# MCU.net
KiCad netlist of a schematic drawn in Altium Designer
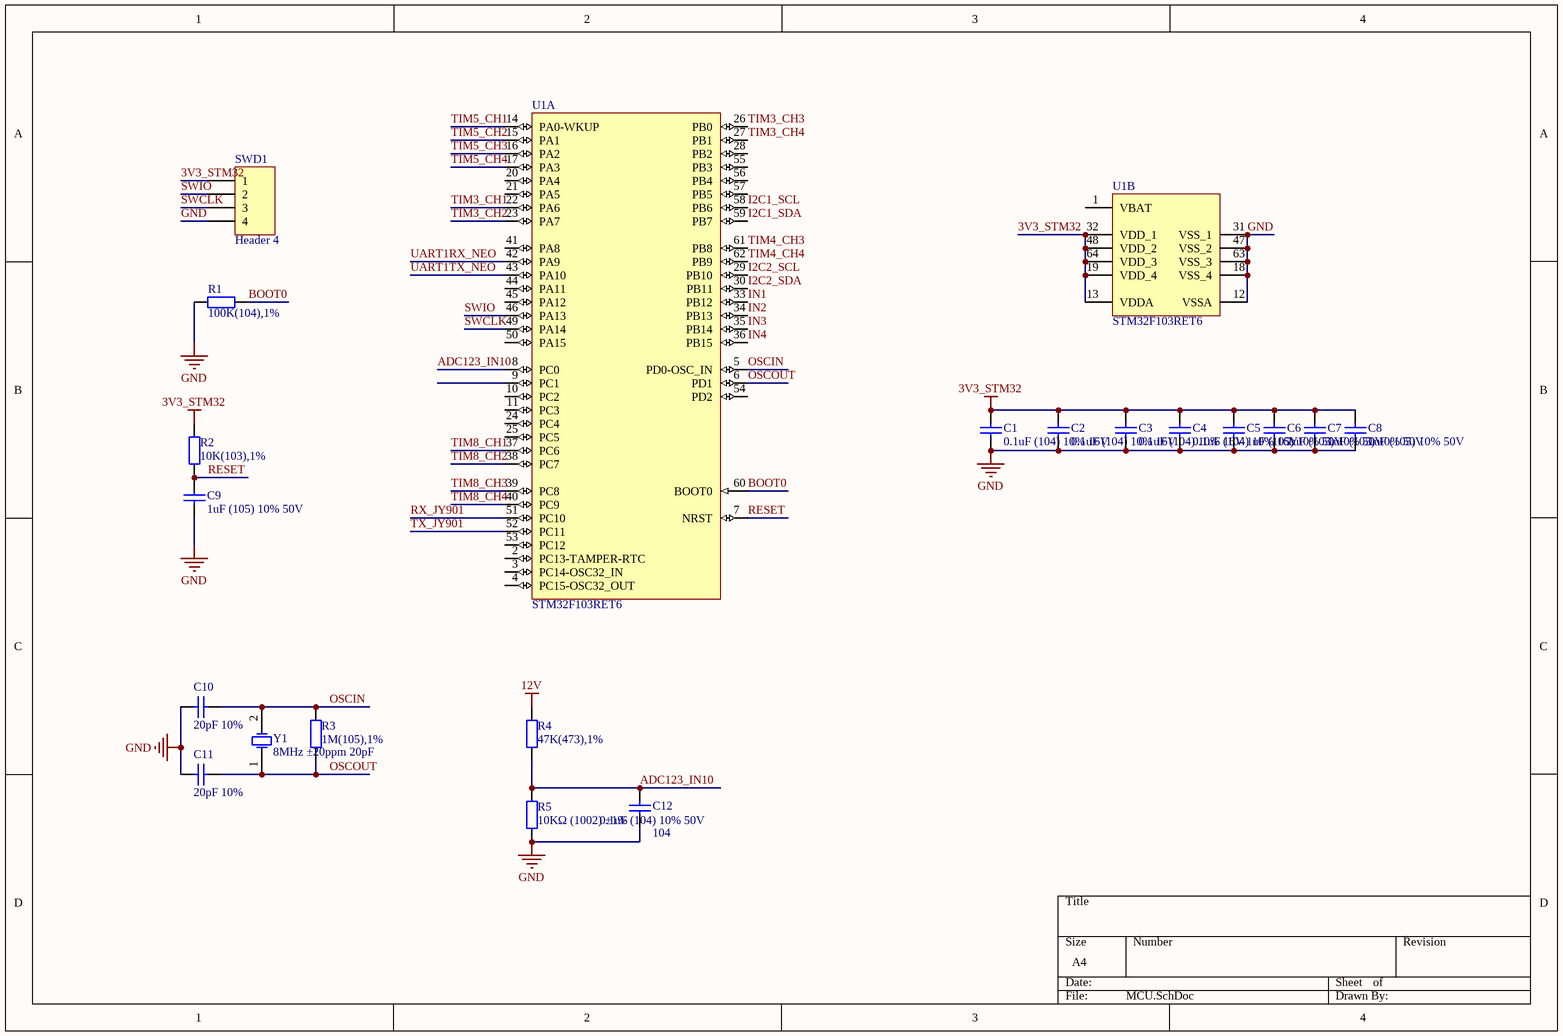
[diagram p0: MCU.SchDoc]

(export (version "E")
  (design (tool "Eeschema 10.0.6"))
  (components
    (comp (ref "C1")
      (value "0.1uF (104) 10% 16V")
      (footprint "0603_C")
      (description "Capacitor")
      (fields (field (name "PUBLISHER") "Altium Limited"))
      (libsource (lib "STM32F103C8T6(原理图库)") (part "Cap"))
    )
    (comp (ref "C2")
      (value "0.1uF (104) 10% 16V")
      (footprint "0603_C")
      (description "Capacitor")
      (fields (field (name "PUBLISHER") "Altium Limited"))
      (libsource (lib "STM32F103C8T6(原理图库)") (part "Cap"))
    )
    (comp (ref "C3")
      (value "0.1uF (104) 10% 16V")
      (footprint "0603_C")
      (description "Capacitor")
      (fields (field (name "PUBLISHER") "Altium Limited"))
      (libsource (lib "STM32F103C8T6(原理图库)") (part "Cap"))
    )
    (comp (ref "C4")
      (value "0.1uF (104) 10% 16V")
      (footprint "0603_C")
      (description "Capacitor")
      (fields (field (name "PUBLISHER") "Altium Limited"))
      (libsource (lib "STM32F103C8T6(原理图库)") (part "Cap"))
    )
    (comp (ref "C5")
      (value "1uF (105) 10% 50V")
      (footprint "0603_C")
      (description "贴片电容")
      (libsource (lib "Miscellaneous Devices LC") (part "0603 1uF (105) 10% 50V"))
    )
    (comp (ref "C6")
      (value "1uF (105) 10% 50V")
      (footprint "0603_C")
      (description "贴片电容")
      (libsource (lib "Miscellaneous Devices LC") (part "0603 1uF (105) 10% 50V"))
    )
    (comp (ref "C7")
      (value "1uF (105) 10% 50V")
      (footprint "0603_C")
      (description "贴片电容")
      (libsource (lib "Miscellaneous Devices LC") (part "0603 1uF (105) 10% 50V"))
    )
    (comp (ref "C8")
      (value "1uF (105) 10% 50V")
      (footprint "0603_C")
      (description "贴片电容")
      (libsource (lib "Miscellaneous Devices LC") (part "0603 1uF (105) 10% 50V"))
    )
    (comp (ref "C9")
      (value "1uF (105) 10% 50V")
      (footprint "0603_C")
      (description "Capacitor")
      (fields (field (name "PUBLISHER") "Altium Limited"))
      (libsource (lib "STM32F103C8T6(原理图库)") (part "Cap"))
    )
    (comp (ref "C10")
      (value "20pF 10%")
      (footprint "0603_C")
      (description "Capacitor")
      (fields (field (name "PUBLISHER") "Altium Limited"))
      (libsource (lib "STM32F103C8T6(原理图库)") (part "Cap"))
    )
    (comp (ref "C11")
      (value "20pF 10%")
      (footprint "0603_C")
      (description "Capacitor")
      (fields (field (name "PUBLISHER") "Altium Limited"))
      (libsource (lib "STM32F103C8T6(原理图库)") (part "Cap"))
    )
    (comp (ref "C12")
      (value "0.1uF (104) 10% 50V")
      (footprint "0603_C")
      (description "Capacitor")
      (fields (field (name "ALTIUM_VALUE") "104") (field (name "PUBLISHER") "Altium Limited"))
      (libsource (lib "Miscellaneous Devices") (part "Cap"))
    )
    (comp (ref "R1")
      (value "100K(104),1%")
      (footprint "0603_R")
      (description "Resistor")
      (fields (field (name "PUBLISHER") "Altium Limited"))
      (libsource (lib "") (part "Res2_1"))
    )
    (comp (ref "R2")
      (value "10K(103),1%")
      (footprint "0603_R")
      (description "Resistor")
      (fields (field (name "PUBLISHER") "Altium Limited"))
      (libsource (lib "STM32F103C8T6(原理图库)") (part "Res2"))
    )
    (comp (ref "R3")
      (value "1M(105),1%")
      (footprint "0603_R")
      (description "Resistor")
      (fields (field (name "PUBLISHER") "Altium Limited"))
      (libsource (lib "STM32F103C8T6(原理图库)") (part "Res2"))
    )
    (comp (ref "R4")
      (value "47K(473),1%")
      (footprint "0603_R")
      (description "Resistor")
      (fields (field (name "PUBLISHER") "Altium Limited"))
      (libsource (lib "STM32F103C8T6(原理图库)") (part "Res2"))
    )
    (comp (ref "R5")
      (value "10KΩ (1002) ±1%")
      (footprint "0603_R")
      (description "贴片电阻")
      (libsource (lib "Miscellaneous Devices LC") (part "0603 10KΩ (1002) 1%"))
    )
    (comp (ref "SWD1")
      (value "Header 4")
      (footprint "HDR1X4")
      (description "Header, 4-Pin")
      (fields (field (name "PUBLISHER") "Altium Limited"))
      (libsource (lib "Miscellaneous Connectors") (part "Header 4"))
    )
    (comp (ref "U1")
      (value "STM32F103RET6")
      (footprint "LQFP-64_10x10x05P")
      (description "ARM")
      (libsource (lib "Miscellaneous Devices LC") (part "STM32F103RET6"))
    )
    (comp (ref "Y1")
      (value "8MHz ±20ppm 20pF")
      (footprint "SMD-5032_2P")
      (description "贴片晶振")
      (libsource (lib "Miscellaneous Devices LC") (part "SMD-5032_2P 8MHz 20ppm 20pF"))
    )
  )
  (nets
    (net (code "1") (name "/ADC123_IN10") (class "Default")
      (node (ref "C12") (pin "2") (pinfunction "2_2") (pintype "passive"))
      (node (ref "R4") (pin "1") (pinfunction "1_1") (pintype "passive"))
      (node (ref "R5") (pin "2") (pinfunction "2_2") (pintype "passive"))
      (node (ref "U1") (pin "8") (pinfunction "PC0_8") (pintype "bidirectional"))
    )
    (net (code "2") (name "/BOOT0") (class "Default")
      (node (ref "R1") (pin "2") (pinfunction "2_2") (pintype "passive"))
      (node (ref "U1") (pin "60") (pinfunction "BOOT0_60") (pintype "input"))
    )
    (net (code "3") (name "/I2C1_SCL") (class "Default")
      (node (ref "U1") (pin "58") (pinfunction "PB6_58") (pintype "bidirectional"))
    )
    (net (code "4") (name "/I2C1_SDA") (class "Default")
      (node (ref "U1") (pin "59") (pinfunction "PB7_59") (pintype "bidirectional"))
    )
    (net (code "5") (name "/I2C2_SCL") (class "Default")
      (node (ref "U1") (pin "29") (pinfunction "PB10_29") (pintype "bidirectional"))
    )
    (net (code "6") (name "/I2C2_SDA") (class "Default")
      (node (ref "U1") (pin "30") (pinfunction "PB11_30") (pintype "bidirectional"))
    )
    (net (code "7") (name "/IN1") (class "Default")
      (node (ref "U1") (pin "33") (pinfunction "PB12_33") (pintype "bidirectional"))
    )
    (net (code "8") (name "/IN2") (class "Default")
      (node (ref "U1") (pin "34") (pinfunction "PB13_34") (pintype "bidirectional"))
    )
    (net (code "9") (name "/IN3") (class "Default")
      (node (ref "U1") (pin "35") (pinfunction "PB14_35") (pintype "bidirectional"))
    )
    (net (code "10") (name "/IN4") (class "Default")
      (node (ref "U1") (pin "36") (pinfunction "PB15_36") (pintype "bidirectional"))
    )
    (net (code "11") (name "/OSCIN") (class "Default")
      (node (ref "C10") (pin "1") (pinfunction "1_1") (pintype "passive"))
      (node (ref "R3") (pin "2") (pinfunction "2_2") (pintype "passive"))
      (node (ref "U1") (pin "5") (pinfunction "PD0-OSC_IN_5") (pintype "bidirectional"))
      (node (ref "Y1") (pin "2") (pinfunction "OSC2_2") (pintype "passive"))
    )
    (net (code "12") (name "/OSCOUT") (class "Default")
      (node (ref "C11") (pin "1") (pinfunction "1_1") (pintype "passive"))
      (node (ref "R3") (pin "1") (pinfunction "1_1") (pintype "passive"))
      (node (ref "U1") (pin "6") (pinfunction "PD1_6") (pintype "bidirectional"))
      (node (ref "Y1") (pin "1") (pinfunction "OSC1_1") (pintype "passive"))
    )
    (net (code "13") (name "/RESET") (class "Default")
      (node (ref "C9") (pin "2") (pinfunction "2_2") (pintype "passive"))
      (node (ref "R2") (pin "1") (pinfunction "1_1") (pintype "passive"))
      (node (ref "U1") (pin "7") (pinfunction "NRST_7") (pintype "bidirectional"))
    )
    (net (code "14") (name "/RX_JY901") (class "Default")
      (node (ref "U1") (pin "51") (pinfunction "PC10_51") (pintype "bidirectional"))
    )
    (net (code "15") (name "/SWCLK") (class "Default")
      (node (ref "SWD1") (pin "3") (pinfunction "3_3") (pintype "passive"))
      (node (ref "U1") (pin "49") (pinfunction "PA14_49") (pintype "bidirectional"))
    )
    (net (code "16") (name "/SWIO") (class "Default")
      (node (ref "SWD1") (pin "2") (pinfunction "2_2") (pintype "passive"))
      (node (ref "U1") (pin "46") (pinfunction "PA13_46") (pintype "bidirectional"))
    )
    (net (code "17") (name "/TIM3_CH1") (class "Default")
      (node (ref "U1") (pin "22") (pinfunction "PA6_22") (pintype "bidirectional"))
    )
    (net (code "18") (name "/TIM3_CH2") (class "Default")
      (node (ref "U1") (pin "23") (pinfunction "PA7_23") (pintype "bidirectional"))
    )
    (net (code "19") (name "/TIM3_CH3") (class "Default")
      (node (ref "U1") (pin "26") (pinfunction "PB0_26") (pintype "bidirectional"))
    )
    (net (code "20") (name "/TIM3_CH4") (class "Default")
      (node (ref "U1") (pin "27") (pinfunction "PB1_27") (pintype "bidirectional"))
    )
    (net (code "21") (name "/TIM4_CH3") (class "Default")
      (node (ref "U1") (pin "61") (pinfunction "PB8_61") (pintype "bidirectional"))
    )
    (net (code "22") (name "/TIM4_CH4") (class "Default")
      (node (ref "U1") (pin "62") (pinfunction "PB9_62") (pintype "bidirectional"))
    )
    (net (code "23") (name "/TIM5_CH1") (class "Default")
      (node (ref "U1") (pin "14") (pinfunction "PA0-WKUP_14") (pintype "bidirectional"))
    )
    (net (code "24") (name "/TIM5_CH2") (class "Default")
      (node (ref "U1") (pin "15") (pinfunction "PA1_15") (pintype "bidirectional"))
    )
    (net (code "25") (name "/TIM5_CH3") (class "Default")
      (node (ref "U1") (pin "16") (pinfunction "PA2_16") (pintype "bidirectional"))
    )
    (net (code "26") (name "/TIM5_CH4") (class "Default")
      (node (ref "U1") (pin "17") (pinfunction "PA3_17") (pintype "bidirectional"))
    )
    (net (code "27") (name "/TIM8_CH1") (class "Default")
      (node (ref "U1") (pin "37") (pinfunction "PC6_37") (pintype "bidirectional"))
    )
    (net (code "28") (name "/TIM8_CH2") (class "Default")
      (node (ref "U1") (pin "38") (pinfunction "PC7_38") (pintype "bidirectional"))
    )
    (net (code "29") (name "/TIM8_CH3") (class "Default")
      (node (ref "U1") (pin "39") (pinfunction "PC8_39") (pintype "bidirectional"))
    )
    (net (code "30") (name "/TIM8_CH4") (class "Default")
      (node (ref "U1") (pin "40") (pinfunction "PC9_40") (pintype "bidirectional"))
    )
    (net (code "31") (name "/TX_JY901") (class "Default")
      (node (ref "U1") (pin "52") (pinfunction "PC11_52") (pintype "bidirectional"))
    )
    (net (code "32") (name "/UART1RX_NEO") (class "Default")
      (node (ref "U1") (pin "42") (pinfunction "PA9_42") (pintype "bidirectional"))
    )
    (net (code "33") (name "/UART1TX_NEO") (class "Default")
      (node (ref "U1") (pin "43") (pinfunction "PA10_43") (pintype "bidirectional"))
    )
    (net (code "34") (name "3V3_STM32") (class "Default")
      (node (ref "C1") (pin "2") (pinfunction "2_2") (pintype "passive"))
      (node (ref "C2") (pin "2") (pinfunction "2_2") (pintype "passive"))
      (node (ref "C3") (pin "2") (pinfunction "2_2") (pintype "passive"))
      (node (ref "C4") (pin "2") (pinfunction "2_2") (pintype "passive"))
      (node (ref "C5") (pin "2") (pinfunction "2_2") (pintype "passive"))
      (node (ref "C6") (pin "2") (pinfunction "2_2") (pintype "passive"))
      (node (ref "C7") (pin "2") (pinfunction "2_2") (pintype "passive"))
      (node (ref "C8") (pin "2") (pinfunction "2_2") (pintype "passive"))
      (node (ref "R2") (pin "2") (pinfunction "2_2") (pintype "passive"))
      (node (ref "SWD1") (pin "1") (pinfunction "1_1") (pintype "passive"))
      (node (ref "U1") (pin "13") (pinfunction "VDDA_13") (pintype "power_in"))
      (node (ref "U1") (pin "19") (pinfunction "VDD_4_19") (pintype "power_in"))
      (node (ref "U1") (pin "32") (pinfunction "VDD_1_32") (pintype "power_in"))
      (node (ref "U1") (pin "48") (pinfunction "VDD_2_48") (pintype "power_in"))
      (node (ref "U1") (pin "64") (pinfunction "VDD_3_64") (pintype "power_in"))
    )
    (net (code "35") (name "12V") (class "Default")
      (node (ref "R4") (pin "2") (pinfunction "2_2") (pintype "passive"))
    )
    (net (code "36") (name "GND") (class "Default")
      (node (ref "C1") (pin "1") (pinfunction "1_1") (pintype "passive"))
      (node (ref "C10") (pin "2") (pinfunction "2_2") (pintype "passive"))
      (node (ref "C11") (pin "2") (pinfunction "2_2") (pintype "passive"))
      (node (ref "C12") (pin "1") (pinfunction "1_1") (pintype "passive"))
      (node (ref "C2") (pin "1") (pinfunction "1_1") (pintype "passive"))
      (node (ref "C3") (pin "1") (pinfunction "1_1") (pintype "passive"))
      (node (ref "C4") (pin "1") (pinfunction "1_1") (pintype "passive"))
      (node (ref "C5") (pin "1") (pinfunction "1_1") (pintype "passive"))
      (node (ref "C6") (pin "1") (pinfunction "1_1") (pintype "passive"))
      (node (ref "C7") (pin "1") (pinfunction "1_1") (pintype "passive"))
      (node (ref "C8") (pin "1") (pinfunction "1_1") (pintype "passive"))
      (node (ref "C9") (pin "1") (pinfunction "1_1") (pintype "passive"))
      (node (ref "R1") (pin "1") (pinfunction "1_1") (pintype "passive"))
      (node (ref "R5") (pin "1") (pinfunction "1_1") (pintype "passive"))
      (node (ref "SWD1") (pin "4") (pinfunction "4_4") (pintype "passive"))
      (node (ref "U1") (pin "12") (pinfunction "VSSA_12") (pintype "power_in"))
      (node (ref "U1") (pin "18") (pinfunction "VSS_4_18") (pintype "power_in"))
      (node (ref "U1") (pin "31") (pinfunction "VSS_1_31") (pintype "power_in"))
      (node (ref "U1") (pin "47") (pinfunction "VSS_2_47") (pintype "power_in"))
      (node (ref "U1") (pin "63") (pinfunction "VSS_3_63") (pintype "power_in"))
    )
    (net (code "37") (name "unconnected-(U1A-PA4-Pad20)") (class "Default")
      (node (ref "U1") (pin "20") (pinfunction "PA4_20") (pintype "bidirectional"))
    )
    (net (code "38") (name "unconnected-(U1A-PA5-Pad21)") (class "Default")
      (node (ref "U1") (pin "21") (pinfunction "PA5_21") (pintype "bidirectional"))
    )
    (net (code "39") (name "unconnected-(U1A-PA8-Pad41)") (class "Default")
      (node (ref "U1") (pin "41") (pinfunction "PA8_41") (pintype "bidirectional"))
    )
    (net (code "40") (name "unconnected-(U1A-PA11-Pad44)") (class "Default")
      (node (ref "U1") (pin "44") (pinfunction "PA11_44") (pintype "bidirectional"))
    )
    (net (code "41") (name "unconnected-(U1A-PA12-Pad45)") (class "Default")
      (node (ref "U1") (pin "45") (pinfunction "PA12_45") (pintype "bidirectional"))
    )
    (net (code "42") (name "unconnected-(U1A-PA15-Pad50)") (class "Default")
      (node (ref "U1") (pin "50") (pinfunction "PA15_50") (pintype "bidirectional"))
    )
    (net (code "43") (name "unconnected-(U1A-PB2-Pad28)") (class "Default")
      (node (ref "U1") (pin "28") (pinfunction "PB2_28") (pintype "bidirectional"))
    )
    (net (code "44") (name "unconnected-(U1A-PB3-Pad55)") (class "Default")
      (node (ref "U1") (pin "55") (pinfunction "PB3_55") (pintype "bidirectional"))
    )
    (net (code "45") (name "unconnected-(U1A-PB4-Pad56)") (class "Default")
      (node (ref "U1") (pin "56") (pinfunction "PB4_56") (pintype "bidirectional"))
    )
    (net (code "46") (name "unconnected-(U1A-PB5-Pad57)") (class "Default")
      (node (ref "U1") (pin "57") (pinfunction "PB5_57") (pintype "bidirectional"))
    )
    (net (code "47") (name "unconnected-(U1A-PC1-Pad9)") (class "Default")
      (node (ref "U1") (pin "9") (pinfunction "PC1_9") (pintype "bidirectional"))
    )
    (net (code "48") (name "unconnected-(U1A-PC2-Pad10)") (class "Default")
      (node (ref "U1") (pin "10") (pinfunction "PC2_10") (pintype "bidirectional"))
    )
    (net (code "49") (name "unconnected-(U1A-PC3-Pad11)") (class "Default")
      (node (ref "U1") (pin "11") (pinfunction "PC3_11") (pintype "bidirectional"))
    )
    (net (code "50") (name "unconnected-(U1A-PC4-Pad24)") (class "Default")
      (node (ref "U1") (pin "24") (pinfunction "PC4_24") (pintype "bidirectional"))
    )
    (net (code "51") (name "unconnected-(U1A-PC5-Pad25)") (class "Default")
      (node (ref "U1") (pin "25") (pinfunction "PC5_25") (pintype "bidirectional"))
    )
    (net (code "52") (name "unconnected-(U1A-PC12-Pad53)") (class "Default")
      (node (ref "U1") (pin "53") (pinfunction "PC12_53") (pintype "bidirectional"))
    )
    (net (code "53") (name "unconnected-(U1A-PC13-TAMPER-RTC-Pad2)") (class "Default")
      (node (ref "U1") (pin "2") (pinfunction "PC13-TAMPER-RTC_2") (pintype "bidirectional"))
    )
    (net (code "54") (name "unconnected-(U1A-PC14-OSC32_IN-Pad3)") (class "Default")
      (node (ref "U1") (pin "3") (pinfunction "PC14-OSC32_IN_3") (pintype "bidirectional"))
    )
    (net (code "55") (name "unconnected-(U1A-PC15-OSC32_OUT-Pad4)") (class "Default")
      (node (ref "U1") (pin "4") (pinfunction "PC15-OSC32_OUT_4") (pintype "bidirectional"))
    )
    (net (code "56") (name "unconnected-(U1A-PD2-Pad54)") (class "Default")
      (node (ref "U1") (pin "54") (pinfunction "PD2_54") (pintype "bidirectional"))
    )
    (net (code "57") (name "unconnected-(U1B-VBAT-Pad1)") (class "Default")
      (node (ref "U1") (pin "1") (pinfunction "VBAT_1") (pintype "power_in"))
    )
  )
)
